# COMM.net
KiCad netlist of a schematic drawn in Altium Designer
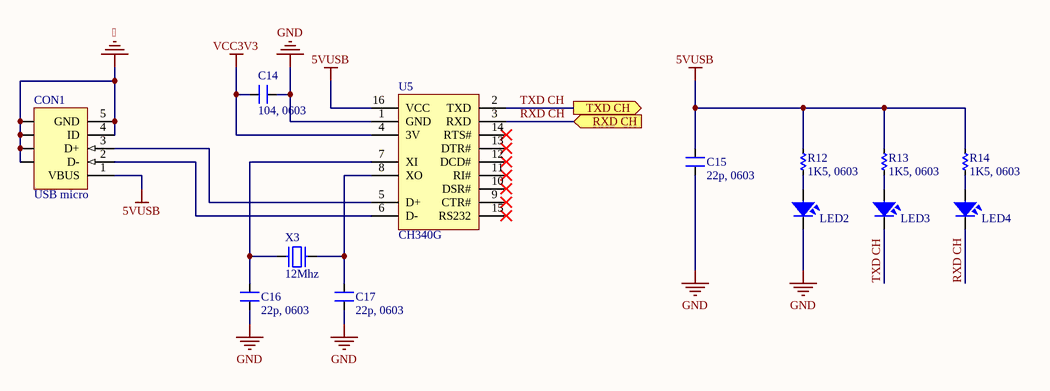
[diagram p0: COMM.SchDoc]

(export (version "E")
  (design (tool "Eeschema 10.0.6"))
  (components
    (comp (ref "C14")
      (value "104, 0603")
      (footprint "SM-0603")
      (description "Cap SMD")
      (libsource (lib "KhanhBK_Library_4") (part "CM"))
    )
    (comp (ref "C15")
      (value "22p, 0603")
      (footprint "SM-0603")
      (description "Cap SMD")
      (libsource (lib "KhanhBK_Library_4") (part "CM"))
    )
    (comp (ref "C16")
      (value "22p, 0603")
      (footprint "SM-0603")
      (description "Cap SMD")
      (libsource (lib "KhanhBK_Library_4") (part "CM"))
    )
    (comp (ref "C17")
      (value "22p, 0603")
      (footprint "SM-0603")
      (description "Cap SMD")
      (libsource (lib "KhanhBK_Library_4") (part "CM"))
    )
    (comp (ref "CON1")
      (value "USB micro")
      (footprint "CONN/USB/MICRO/RA")
      (description "USB micro, 5 pins")
      (libsource (lib "connectors") (part "CON USB micro"))
    )
    (comp (ref "LED2")
      (value "LED")
      (footprint "LED-0805-Blue")
      (libsource (lib "KhanhBK_SCH_Library_1") (part "LED SMD"))
    )
    (comp (ref "LED3")
      (value "LED")
      (footprint "LED-0805-Blue")
      (libsource (lib "KhanhBK_SCH_Library_1") (part "LED SMD"))
    )
    (comp (ref "LED4")
      (value "LED")
      (footprint "LED-0805-Blue")
      (libsource (lib "KhanhBK_SCH_Library_1") (part "LED SMD"))
    )
    (comp (ref "R12")
      (value "1K5, 0603")
      (footprint "RES-SMD-0603")
      (description "Resistor")
      (fields
        (field (name "MANUFACTURER") "Generic Components")
        (field (name "PUBLISHER") "Altium Hobart Technology Centre")
      )
      (libsource (lib "KhanhBK_SCH_Library_1") (part "Res-SMD"))
    )
    (comp (ref "R13")
      (value "1K5, 0603")
      (footprint "RES-SMD-0603")
      (description "Resistor")
      (fields
        (field (name "MANUFACTURER") "Generic Components")
        (field (name "PUBLISHER") "Altium Hobart Technology Centre")
      )
      (libsource (lib "KhanhBK_SCH_Library_1") (part "Res-SMD"))
    )
    (comp (ref "R14")
      (value "1K5, 0603")
      (footprint "RES-SMD-0603")
      (description "Resistor")
      (fields
        (field (name "MANUFACTURER") "Generic Components")
        (field (name "PUBLISHER") "Altium Hobart Technology Centre")
      )
      (libsource (lib "KhanhBK_SCH_Library_1") (part "Res-SMD"))
    )
    (comp (ref "U5")
      (value "CH340G")
      (footprint "SO16")
      (description "High and Low Side Driver")
      (fields (field (name "PUBLISHER") "Altium Limited"))
      (libsource (lib "KhanhBK_SCH_Library_1") (part "CH340G"))
    )
    (comp (ref "X3")
      (value "12Mhz")
      (footprint "XT2")
      (description "Crystal, 32.768 KHz, -40 to 85 degC, 3.2 x 1.5 x 0.9 mm SMD")
      (libsource (lib "KhanhBK_SCH_Library_1") (part "XT2"))
    )
  )
  (nets
    (net (code "1") (name "") (class "Default")
      (node (ref "CON1") (pin "4") (pinfunction "ID_4") (pintype "passive"))
      (node (ref "CON1") (pin "5") (pinfunction "GND_5") (pintype "power_in"))
      (node (ref "CON1") (pin "6") (pinfunction "SHLD_6") (pintype "passive"))
      (node (ref "CON1") (pin "7") (pinfunction "SHLD_7") (pintype "passive"))
      (node (ref "CON1") (pin "8") (pinfunction "SHLD_8") (pintype "passive"))
      (node (ref "CON1") (pin "9") (pinfunction "SHLD_9") (pintype "passive"))
    )
    (net (code "2") (name "/RXD CH") (class "Default")
      (node (ref "LED4") (pin "2") (pinfunction "2_2") (pintype "passive"))
      (node (ref "U5") (pin "3") (pinfunction "RXD_3") (pintype "passive"))
    )
    (net (code "3") (name "/TXD CH") (class "Default")
      (node (ref "LED3") (pin "2") (pinfunction "2_2") (pintype "passive"))
      (node (ref "U5") (pin "2") (pinfunction "TXD_2") (pintype "passive"))
    )
    (net (code "4") (name "5VUSB") (class "Default")
      (node (ref "C15") (pin "2") (pinfunction "2_2") (pintype "passive"))
      (node (ref "CON1") (pin "1") (pinfunction "VBUS_1") (pintype "power_in"))
      (node (ref "R12") (pin "1") (pinfunction "1_1") (pintype "passive"))
      (node (ref "R13") (pin "1") (pinfunction "1_1") (pintype "passive"))
      (node (ref "R14") (pin "1") (pinfunction "1_1") (pintype "passive"))
      (node (ref "U5") (pin "16") (pinfunction "VCC_16") (pintype "passive"))
    )
    (net (code "5") (name "GND") (class "Default")
      (node (ref "C14") (pin "1") (pinfunction "1_1") (pintype "passive"))
      (node (ref "C15") (pin "1") (pinfunction "1_1") (pintype "passive"))
      (node (ref "C16") (pin "1") (pinfunction "1_1") (pintype "passive"))
      (node (ref "C17") (pin "1") (pinfunction "1_1") (pintype "passive"))
      (node (ref "LED2") (pin "2") (pinfunction "2_2") (pintype "passive"))
      (node (ref "U5") (pin "1") (pinfunction "GND_1") (pintype "passive"))
    )
    (net (code "6") (name "Net-(CON1-D+)") (class "Default")
      (node (ref "CON1") (pin "3") (pinfunction "D+_3") (pintype "input"))
      (node (ref "U5") (pin "5") (pinfunction "D+_5") (pintype "passive"))
    )
    (net (code "7") (name "Net-(CON1-D-)") (class "Default")
      (node (ref "CON1") (pin "2") (pinfunction "D-_2") (pintype "input"))
      (node (ref "U5") (pin "6") (pinfunction "D-_6") (pintype "passive"))
    )
    (net (code "8") (name "Net-(LED2-Pad1)") (class "Default")
      (node (ref "LED2") (pin "1") (pinfunction "1_1") (pintype "passive"))
      (node (ref "R12") (pin "2") (pinfunction "2_2") (pintype "passive"))
    )
    (net (code "9") (name "Net-(LED3-Pad1)") (class "Default")
      (node (ref "LED3") (pin "1") (pinfunction "1_1") (pintype "passive"))
      (node (ref "R13") (pin "2") (pinfunction "2_2") (pintype "passive"))
    )
    (net (code "10") (name "Net-(LED4-Pad1)") (class "Default")
      (node (ref "LED4") (pin "1") (pinfunction "1_1") (pintype "passive"))
      (node (ref "R14") (pin "2") (pinfunction "2_2") (pintype "passive"))
    )
    (net (code "11") (name "Net-(U5-XI)") (class "Default")
      (node (ref "C16") (pin "2") (pinfunction "2_2") (pintype "passive"))
      (node (ref "U5") (pin "7") (pinfunction "XI_7") (pintype "passive"))
      (node (ref "X3") (pin "1") (pinfunction "1_1") (pintype "passive"))
    )
    (net (code "12") (name "Net-(U5-XO)") (class "Default")
      (node (ref "C17") (pin "2") (pinfunction "2_2") (pintype "passive"))
      (node (ref "U5") (pin "8") (pinfunction "XO_8") (pintype "passive"))
      (node (ref "X3") (pin "2") (pinfunction "2_2") (pintype "passive"))
    )
    (net (code "13") (name "VCC3V3") (class "Default")
      (node (ref "C14") (pin "2") (pinfunction "2_2") (pintype "passive"))
      (node (ref "U5") (pin "4") (pinfunction "3V_4") (pintype "passive"))
    )
    (net (code "14") (name "unconnected-(U5-CTR#-Pad9)") (class "Default")
      (node (ref "U5") (pin "9") (pinfunction "CTR#_9") (pintype "passive+no_connect"))
    )
    (net (code "15") (name "unconnected-(U5-DCD#-Pad12)") (class "Default")
      (node (ref "U5") (pin "12") (pinfunction "DCD#_12") (pintype "passive+no_connect"))
    )
    (net (code "16") (name "unconnected-(U5-DSR#-Pad10)") (class "Default")
      (node (ref "U5") (pin "10") (pinfunction "DSR#_10") (pintype "passive+no_connect"))
    )
    (net (code "17") (name "unconnected-(U5-DTR#-Pad13)") (class "Default")
      (node (ref "U5") (pin "13") (pinfunction "DTR#_13") (pintype "passive+no_connect"))
    )
    (net (code "18") (name "unconnected-(U5-RI#-Pad11)") (class "Default")
      (node (ref "U5") (pin "11") (pinfunction "RI#_11") (pintype "passive+no_connect"))
    )
    (net (code "19") (name "unconnected-(U5-RS232-Pad15)") (class "Default")
      (node (ref "U5") (pin "15") (pinfunction "RS232_15") (pintype "passive+no_connect"))
    )
    (net (code "20") (name "unconnected-(U5-RTS#-Pad14)") (class "Default")
      (node (ref "U5") (pin "14") (pinfunction "RTS#_14") (pintype "passive+no_connect"))
    )
  )
)
